# HVIBDC.net
KiCad netlist of a schematic drawn in EAGLE
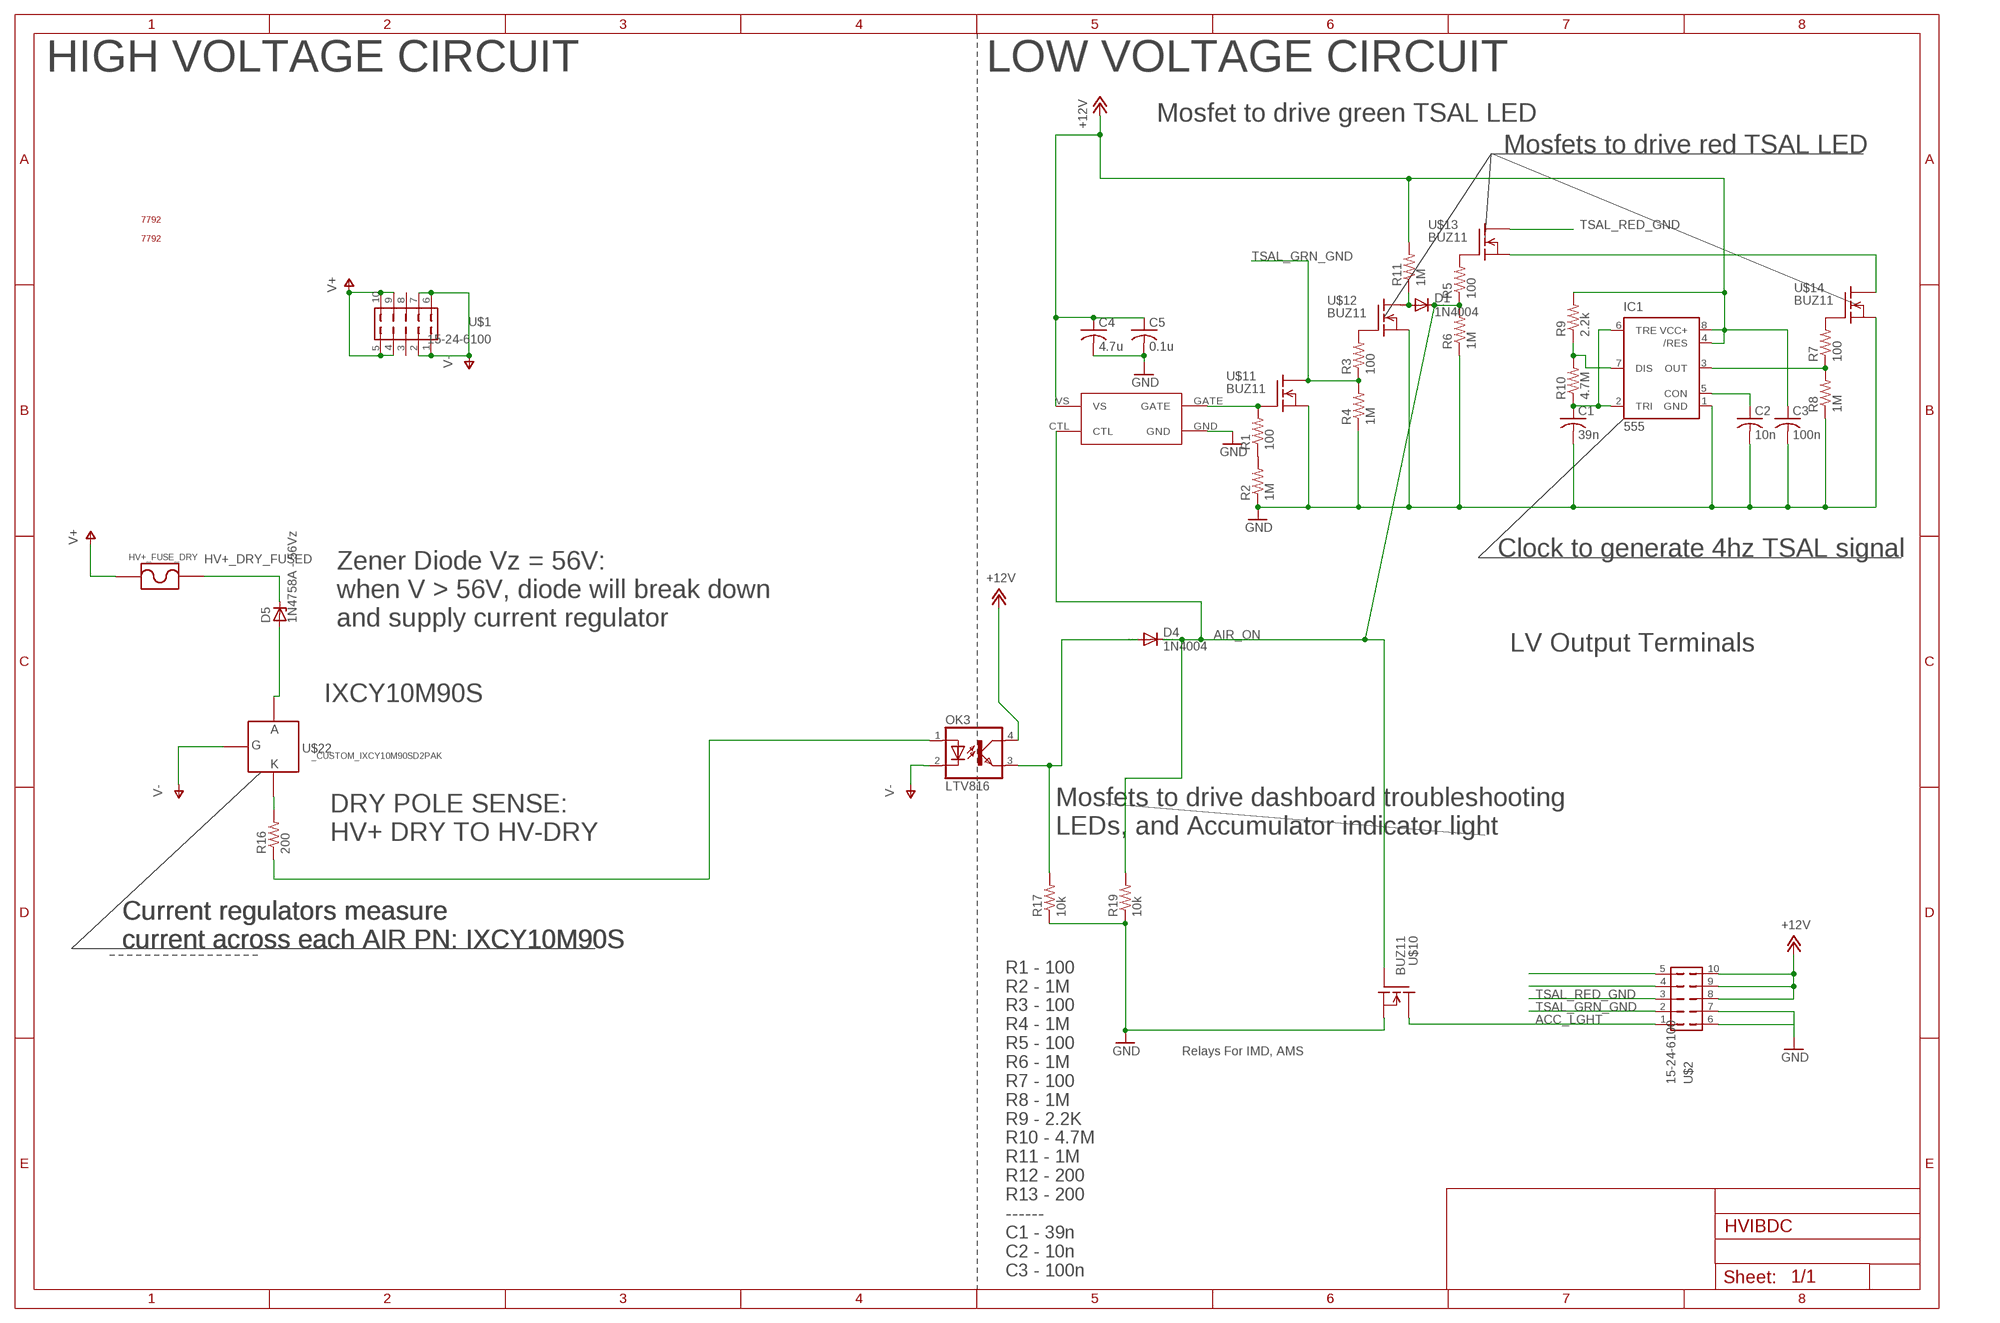
[diagram p0: schematic, sheet 1]

(export (version "E")
  (design (tool "Eeschema 10.0.6"))
  (components
    (comp (ref "C1")
      (value "39n")
      (footprint "eagle-import:C0805")
      (libsource (lib "eagle-import") (part "C-USC0805"))
    )
    (comp (ref "C2")
      (value "10n")
      (footprint "eagle-import:C0805")
      (libsource (lib "eagle-import") (part "C-USC0805"))
    )
    (comp (ref "C3")
      (value "100n")
      (footprint "eagle-import:C0805")
      (libsource (lib "eagle-import") (part "C-USC0805"))
    )
    (comp (ref "C4")
      (value "4.7u")
      (footprint "eagle-import:C0805")
      (libsource (lib "eagle-import") (part "C-USC0805"))
    )
    (comp (ref "C5")
      (value "0.1u")
      (footprint "eagle-import:C0805")
      (libsource (lib "eagle-import") (part "C-USC0805"))
    )
    (comp (ref "D1")
      (value "1N4004")
      (footprint "eagle-import:DO41-10")
      (libsource (lib "eagle-import") (part "1N4004"))
    )
    (comp (ref "D4")
      (value "1N4004")
      (footprint "eagle-import:DO41-10")
      (libsource (lib "eagle-import") (part "1N4004"))
    )
    (comp (ref "D5")
      (value "1N4758A - 56Vz")
      (footprint "eagle-import:ZDIO12.5")
      (libsource (lib "eagle-import") (part "ZENER-DIODEZD-12.5"))
    )
    (comp (ref "HV+_FUSE_DRY")
      (value "_CUSTOM_PARTS_LF_885")
      (footprint "eagle-import:_CUSTOM_PARTS_LF_885")
      (libsource (lib "eagle-import") (part "_CUSTOM_PARTS_LF_885"))
    )
    (comp (ref "IC1")
      (value "555")
      (footprint "eagle-import:DIP08")
      (libsource (lib "eagle-import") (part "555P"))
    )
    (comp (ref "OK3")
      (value "LTV816")
      (footprint "eagle-import:DIL04")
      (libsource (lib "eagle-import") (part "LTV816"))
    )
    (comp (ref "R1")
      (value "100")
      (footprint "eagle-import:R0805")
      (libsource (lib "eagle-import") (part "resistor_348_R-US_R0805"))
    )
    (comp (ref "R2")
      (value "1M")
      (footprint "eagle-import:R0805")
      (libsource (lib "eagle-import") (part "resistor_348_R-US_R0805"))
    )
    (comp (ref "R3")
      (value "100")
      (footprint "eagle-import:R0805")
      (libsource (lib "eagle-import") (part "resistor_348_R-US_R0805"))
    )
    (comp (ref "R4")
      (value "1M")
      (footprint "eagle-import:R0805")
      (libsource (lib "eagle-import") (part "resistor_348_R-US_R0805"))
    )
    (comp (ref "R5")
      (value "100")
      (footprint "eagle-import:R0805")
      (libsource (lib "eagle-import") (part "resistor_348_R-US_R0805"))
    )
    (comp (ref "R6")
      (value "1M")
      (footprint "eagle-import:R0805")
      (libsource (lib "eagle-import") (part "resistor_348_R-US_R0805"))
    )
    (comp (ref "R7")
      (value "100")
      (footprint "eagle-import:R0805")
      (libsource (lib "eagle-import") (part "resistor_348_R-US_R0805"))
    )
    (comp (ref "R8")
      (value "1M")
      (footprint "eagle-import:R0805")
      (libsource (lib "eagle-import") (part "resistor_348_R-US_R0805"))
    )
    (comp (ref "R9")
      (value "2.2k")
      (footprint "eagle-import:R0805")
      (libsource (lib "eagle-import") (part "resistor_348_R-US_R0805"))
    )
    (comp (ref "R10")
      (value "4.7M")
      (footprint "eagle-import:R0805")
      (libsource (lib "eagle-import") (part "resistor_348_R-US_R0805"))
    )
    (comp (ref "R11")
      (value "1M")
      (footprint "eagle-import:R0805")
      (libsource (lib "eagle-import") (part "resistor_348_R-US_R0805"))
    )
    (comp (ref "R16")
      (value "200")
      (footprint "eagle-import:R2010")
      (libsource (lib "eagle-import") (part "R-US_R2010"))
    )
    (comp (ref "R17")
      (value "10k")
      (footprint "eagle-import:R0805")
      (libsource (lib "eagle-import") (part "resistor_348_R-US_R0805"))
    )
    (comp (ref "R19")
      (value "10k")
      (footprint "eagle-import:R0805")
      (libsource (lib "eagle-import") (part "resistor_348_R-US_R0805"))
    )
    (comp (ref "U$1")
      (value "15-24-6100")
      (footprint "eagle-import:15-24-6100")
      (libsource (lib "eagle-import") (part "15-24-6100"))
    )
    (comp (ref "U$2")
      (value "15-24-6100")
      (footprint "eagle-import:15-24-6100")
      (libsource (lib "eagle-import") (part "15-24-6100"))
    )
    (comp (ref "U$3")
      (value "7792")
      (footprint "eagle-import:7792")
      (libsource (lib "eagle-import") (part "7792"))
    )
    (comp (ref "U$4")
      (value "7792")
      (footprint "eagle-import:7792")
      (libsource (lib "eagle-import") (part "7792"))
    )
    (comp (ref "U$10")
      (value "BUZ11")
      (footprint "eagle-import:TO220")
      (libsource (lib "eagle-import") (part "BUZ11"))
    )
    (comp (ref "U$11")
      (value "BUZ11")
      (footprint "eagle-import:TO220")
      (libsource (lib "eagle-import") (part "BUZ11"))
    )
    (comp (ref "U$12")
      (value "BUZ11")
      (footprint "eagle-import:TO220")
      (libsource (lib "eagle-import") (part "BUZ11"))
    )
    (comp (ref "U$13")
      (value "BUZ11")
      (footprint "eagle-import:TO220")
      (libsource (lib "eagle-import") (part "BUZ11"))
    )
    (comp (ref "U$14")
      (value "BUZ11")
      (footprint "eagle-import:TO220")
      (libsource (lib "eagle-import") (part "BUZ11"))
    )
    (comp (ref "U$15")
      (value "MIC4417")
      (footprint "eagle-import:PDM_2019_REVB_MIC4416YM4-TR")
      (libsource (lib "eagle-import") (part "MIC4417"))
    )
    (comp (ref "U$22")
      (value "_CUSTOM_IXCY10M90SD2PAK")
      (footprint "eagle-import:TO228P991X238-3")
      (libsource (lib "eagle-import") (part "_CUSTOM_IXCY10M90SD2PAK"))
    )
  )
  (nets
    (net (code "1") (name "+12V") (class "Default")
      (node (ref "C3") (pin "1") (pinfunction "1_1") (pintype "passive"))
      (node (ref "C4") (pin "1") (pinfunction "1_1") (pintype "passive"))
      (node (ref "C5") (pin "1") (pinfunction "1_1") (pintype "passive"))
      (node (ref "IC1") (pin "4") (pinfunction "/RES_4") (pintype "input"))
      (node (ref "IC1") (pin "8") (pinfunction "VCC+_8") (pintype "power_in"))
      (node (ref "OK3") (pin "4") (pinfunction "COL_4") (pintype "passive"))
      (node (ref "R11") (pin "2") (pinfunction "2_2") (pintype "passive"))
      (node (ref "R9") (pin "2") (pinfunction "2_2") (pintype "passive"))
      (node (ref "U$15") (pin "VS") (pinfunction "VS_VS") (pintype "bidirectional"))
      (node (ref "U$2") (pin "10") (pinfunction "10_10") (pintype "passive"))
      (node (ref "U$2") (pin "8") (pinfunction "8_8") (pintype "passive"))
      (node (ref "U$2") (pin "9") (pinfunction "9_9") (pintype "passive"))
    )
    (net (code "2") (name "/ACC_LGHT") (class "Default")
      (node (ref "U$10") (pin "2") (pinfunction "D_2") (pintype "passive"))
      (node (ref "U$2") (pin "1") (pinfunction "1_1") (pintype "passive"))
    )
    (net (code "3") (name "/AIR_ON") (class "Default")
      (node (ref "D1") (pin "C") (pinfunction "C_C") (pintype "passive"))
      (node (ref "D4") (pin "C") (pinfunction "C_C") (pintype "passive"))
      (node (ref "R19") (pin "2") (pinfunction "2_2") (pintype "passive"))
      (node (ref "R5") (pin "1") (pinfunction "1_1") (pintype "passive"))
      (node (ref "R6") (pin "2") (pinfunction "2_2") (pintype "passive"))
      (node (ref "U$10") (pin "1") (pinfunction "G_1") (pintype "passive"))
      (node (ref "U$15") (pin "CTL") (pinfunction "CTL_CTL") (pintype "bidirectional"))
    )
    (net (code "4") (name "/HV+_DRY_FUSED") (class "Default")
      (node (ref "D5") (pin "C") (pinfunction "C_C") (pintype "passive"))
      (node (ref "HV+_FUSE_DRY") (pin "P$1") (pinfunction "P$1_P$1") (pintype "bidirectional"))
    )
    (net (code "5") (name "/TSAL_GRN_GND") (class "Default")
      (node (ref "R3") (pin "1") (pinfunction "1_1") (pintype "passive"))
      (node (ref "R4") (pin "2") (pinfunction "2_2") (pintype "passive"))
      (node (ref "U$11") (pin "2") (pinfunction "D_2") (pintype "passive"))
      (node (ref "U$2") (pin "2") (pinfunction "2_2") (pintype "passive"))
    )
    (net (code "6") (name "/TSAL_RED_GND") (class "Default")
      (node (ref "U$13") (pin "2") (pinfunction "D_2") (pintype "passive"))
      (node (ref "U$2") (pin "3") (pinfunction "3_3") (pintype "passive"))
    )
    (net (code "7") (name "GND") (class "Default")
      (node (ref "C1") (pin "2") (pinfunction "2_2") (pintype "passive"))
      (node (ref "C2") (pin "2") (pinfunction "2_2") (pintype "passive"))
      (node (ref "C3") (pin "2") (pinfunction "2_2") (pintype "passive"))
      (node (ref "C4") (pin "2") (pinfunction "2_2") (pintype "passive"))
      (node (ref "C5") (pin "2") (pinfunction "2_2") (pintype "passive"))
      (node (ref "IC1") (pin "1") (pinfunction "GND_1") (pintype "power_in"))
      (node (ref "R17") (pin "1") (pinfunction "1_1") (pintype "passive"))
      (node (ref "R19") (pin "1") (pinfunction "1_1") (pintype "passive"))
      (node (ref "R2") (pin "1") (pinfunction "1_1") (pintype "passive"))
      (node (ref "R4") (pin "1") (pinfunction "1_1") (pintype "passive"))
      (node (ref "R6") (pin "1") (pinfunction "1_1") (pintype "passive"))
      (node (ref "R8") (pin "1") (pinfunction "1_1") (pintype "passive"))
      (node (ref "U$10") (pin "3") (pinfunction "S_3") (pintype "passive"))
      (node (ref "U$11") (pin "3") (pinfunction "S_3") (pintype "passive"))
      (node (ref "U$12") (pin "3") (pinfunction "S_3") (pintype "passive"))
      (node (ref "U$14") (pin "3") (pinfunction "S_3") (pintype "passive"))
      (node (ref "U$15") (pin "GND") (pinfunction "GND_GND") (pintype "bidirectional"))
      (node (ref "U$2") (pin "7") (pinfunction "7_7") (pintype "passive"))
    )
    (net (code "8") (name "Net-(IC1-CON)") (class "Default")
      (node (ref "C2") (pin "1") (pinfunction "1_1") (pintype "passive"))
      (node (ref "IC1") (pin "5") (pinfunction "CON_5") (pintype "input"))
    )
    (net (code "9") (name "Net-(IC1-DIS)") (class "Default")
      (node (ref "IC1") (pin "7") (pinfunction "DIS_7") (pintype "input"))
      (node (ref "R10") (pin "2") (pinfunction "2_2") (pintype "passive"))
      (node (ref "R9") (pin "1") (pinfunction "1_1") (pintype "passive"))
    )
    (net (code "10") (name "Net-(IC1-OUT)") (class "Default")
      (node (ref "IC1") (pin "3") (pinfunction "OUT_3") (pintype "output"))
      (node (ref "R7") (pin "1") (pinfunction "1_1") (pintype "passive"))
      (node (ref "R8") (pin "2") (pinfunction "2_2") (pintype "passive"))
    )
    (net (code "11") (name "Net-(IC1-TRE)") (class "Default")
      (node (ref "C1") (pin "1") (pinfunction "1_1") (pintype "passive"))
      (node (ref "IC1") (pin "2") (pinfunction "TRI_2") (pintype "input"))
      (node (ref "IC1") (pin "6") (pinfunction "TRE_6") (pintype "input"))
      (node (ref "R10") (pin "1") (pinfunction "1_1") (pintype "passive"))
    )
    (net (code "12") (name "Net-(OK3-A)") (class "Default")
      (node (ref "OK3") (pin "1") (pinfunction "A_1") (pintype "passive"))
      (node (ref "R16") (pin "1") (pinfunction "1_1") (pintype "passive"))
    )
    (net (code "13") (name "Net-(OK3-EMIT)") (class "Default")
      (node (ref "D4") (pin "A") (pinfunction "A_A") (pintype "passive"))
      (node (ref "OK3") (pin "3") (pinfunction "EMIT_3") (pintype "passive"))
      (node (ref "R17") (pin "2") (pinfunction "2_2") (pintype "passive"))
    )
    (net (code "14") (name "Net-(R1-Pad1)") (class "Default")
      (node (ref "R1") (pin "1") (pinfunction "1_1") (pintype "passive"))
      (node (ref "R2") (pin "2") (pinfunction "2_2") (pintype "passive"))
    )
    (net (code "15") (name "Net-(U$11-G)") (class "Default")
      (node (ref "R1") (pin "2") (pinfunction "2_2") (pintype "passive"))
      (node (ref "U$11") (pin "1") (pinfunction "G_1") (pintype "passive"))
      (node (ref "U$15") (pin "GATE") (pinfunction "GATE_GATE") (pintype "bidirectional"))
    )
    (net (code "16") (name "Net-(U$12-D)") (class "Default")
      (node (ref "D1") (pin "A") (pinfunction "A_A") (pintype "passive"))
      (node (ref "R11") (pin "1") (pinfunction "1_1") (pintype "passive"))
      (node (ref "U$12") (pin "2") (pinfunction "D_2") (pintype "passive"))
    )
    (net (code "17") (name "Net-(U$12-G)") (class "Default")
      (node (ref "R3") (pin "2") (pinfunction "2_2") (pintype "passive"))
      (node (ref "U$12") (pin "1") (pinfunction "G_1") (pintype "passive"))
    )
    (net (code "18") (name "Net-(U$13-G)") (class "Default")
      (node (ref "R5") (pin "2") (pinfunction "2_2") (pintype "passive"))
      (node (ref "U$13") (pin "1") (pinfunction "G_1") (pintype "passive"))
    )
    (net (code "19") (name "Net-(U$13-S)") (class "Default")
      (node (ref "U$13") (pin "3") (pinfunction "S_3") (pintype "passive"))
      (node (ref "U$14") (pin "2") (pinfunction "D_2") (pintype "passive"))
    )
    (net (code "20") (name "Net-(U$14-G)") (class "Default")
      (node (ref "R7") (pin "2") (pinfunction "2_2") (pintype "passive"))
      (node (ref "U$14") (pin "1") (pinfunction "G_1") (pintype "passive"))
    )
    (net (code "21") (name "Net-(U$22-A)") (class "Default")
      (node (ref "D5") (pin "A") (pinfunction "A_A") (pintype "passive"))
      (node (ref "U$22") (pin "3") (pinfunction "A_3") (pintype "bidirectional"))
    )
    (net (code "22") (name "Net-(U$22-K)") (class "Default")
      (node (ref "R16") (pin "2") (pinfunction "2_2") (pintype "passive"))
      (node (ref "U$22") (pin "2") (pinfunction "K_2") (pintype "bidirectional"))
    )
    (net (code "23") (name "V+") (class "Default")
      (node (ref "HV+_FUSE_DRY") (pin "P$2") (pinfunction "P$2_P$2") (pintype "bidirectional"))
      (node (ref "U$1") (pin "10") (pinfunction "10_10") (pintype "passive"))
      (node (ref "U$1") (pin "4") (pinfunction "4_4") (pintype "passive"))
      (node (ref "U$1") (pin "5") (pinfunction "5_5") (pintype "passive"))
      (node (ref "U$1") (pin "9") (pinfunction "9_9") (pintype "passive"))
    )
    (net (code "24") (name "V-") (class "Default")
      (node (ref "OK3") (pin "2") (pinfunction "C_2") (pintype "passive"))
      (node (ref "U$1") (pin "1") (pinfunction "1_1") (pintype "passive"))
      (node (ref "U$1") (pin "2") (pinfunction "2_2") (pintype "passive"))
      (node (ref "U$1") (pin "6") (pinfunction "6_6") (pintype "passive"))
      (node (ref "U$1") (pin "7") (pinfunction "7_7") (pintype "passive"))
      (node (ref "U$22") (pin "1") (pinfunction "G_1") (pintype "bidirectional"))
    )
    (net (code "25") (name "unconnected-(U$1-Pad3)") (class "Default")
      (node (ref "U$1") (pin "3") (pinfunction "3_3") (pintype "passive"))
    )
    (net (code "26") (name "unconnected-(U$1-Pad8)") (class "Default")
      (node (ref "U$1") (pin "8") (pinfunction "8_8") (pintype "passive"))
    )
    (net (code "27") (name "unconnected-(U$2-Pad4)") (class "Default")
      (node (ref "U$2") (pin "4") (pinfunction "4_4") (pintype "passive"))
    )
    (net (code "28") (name "unconnected-(U$2-Pad5)") (class "Default")
      (node (ref "U$2") (pin "5") (pinfunction "5_5") (pintype "passive"))
    )
    (net (code "29") (name "unconnected-(U$2-Pad6)") (class "Default")
      (node (ref "U$2") (pin "6") (pinfunction "6_6") (pintype "passive"))
    )
  )
)
